# USB-PD.net
KiCad netlist of a schematic drawn in Altium Designer
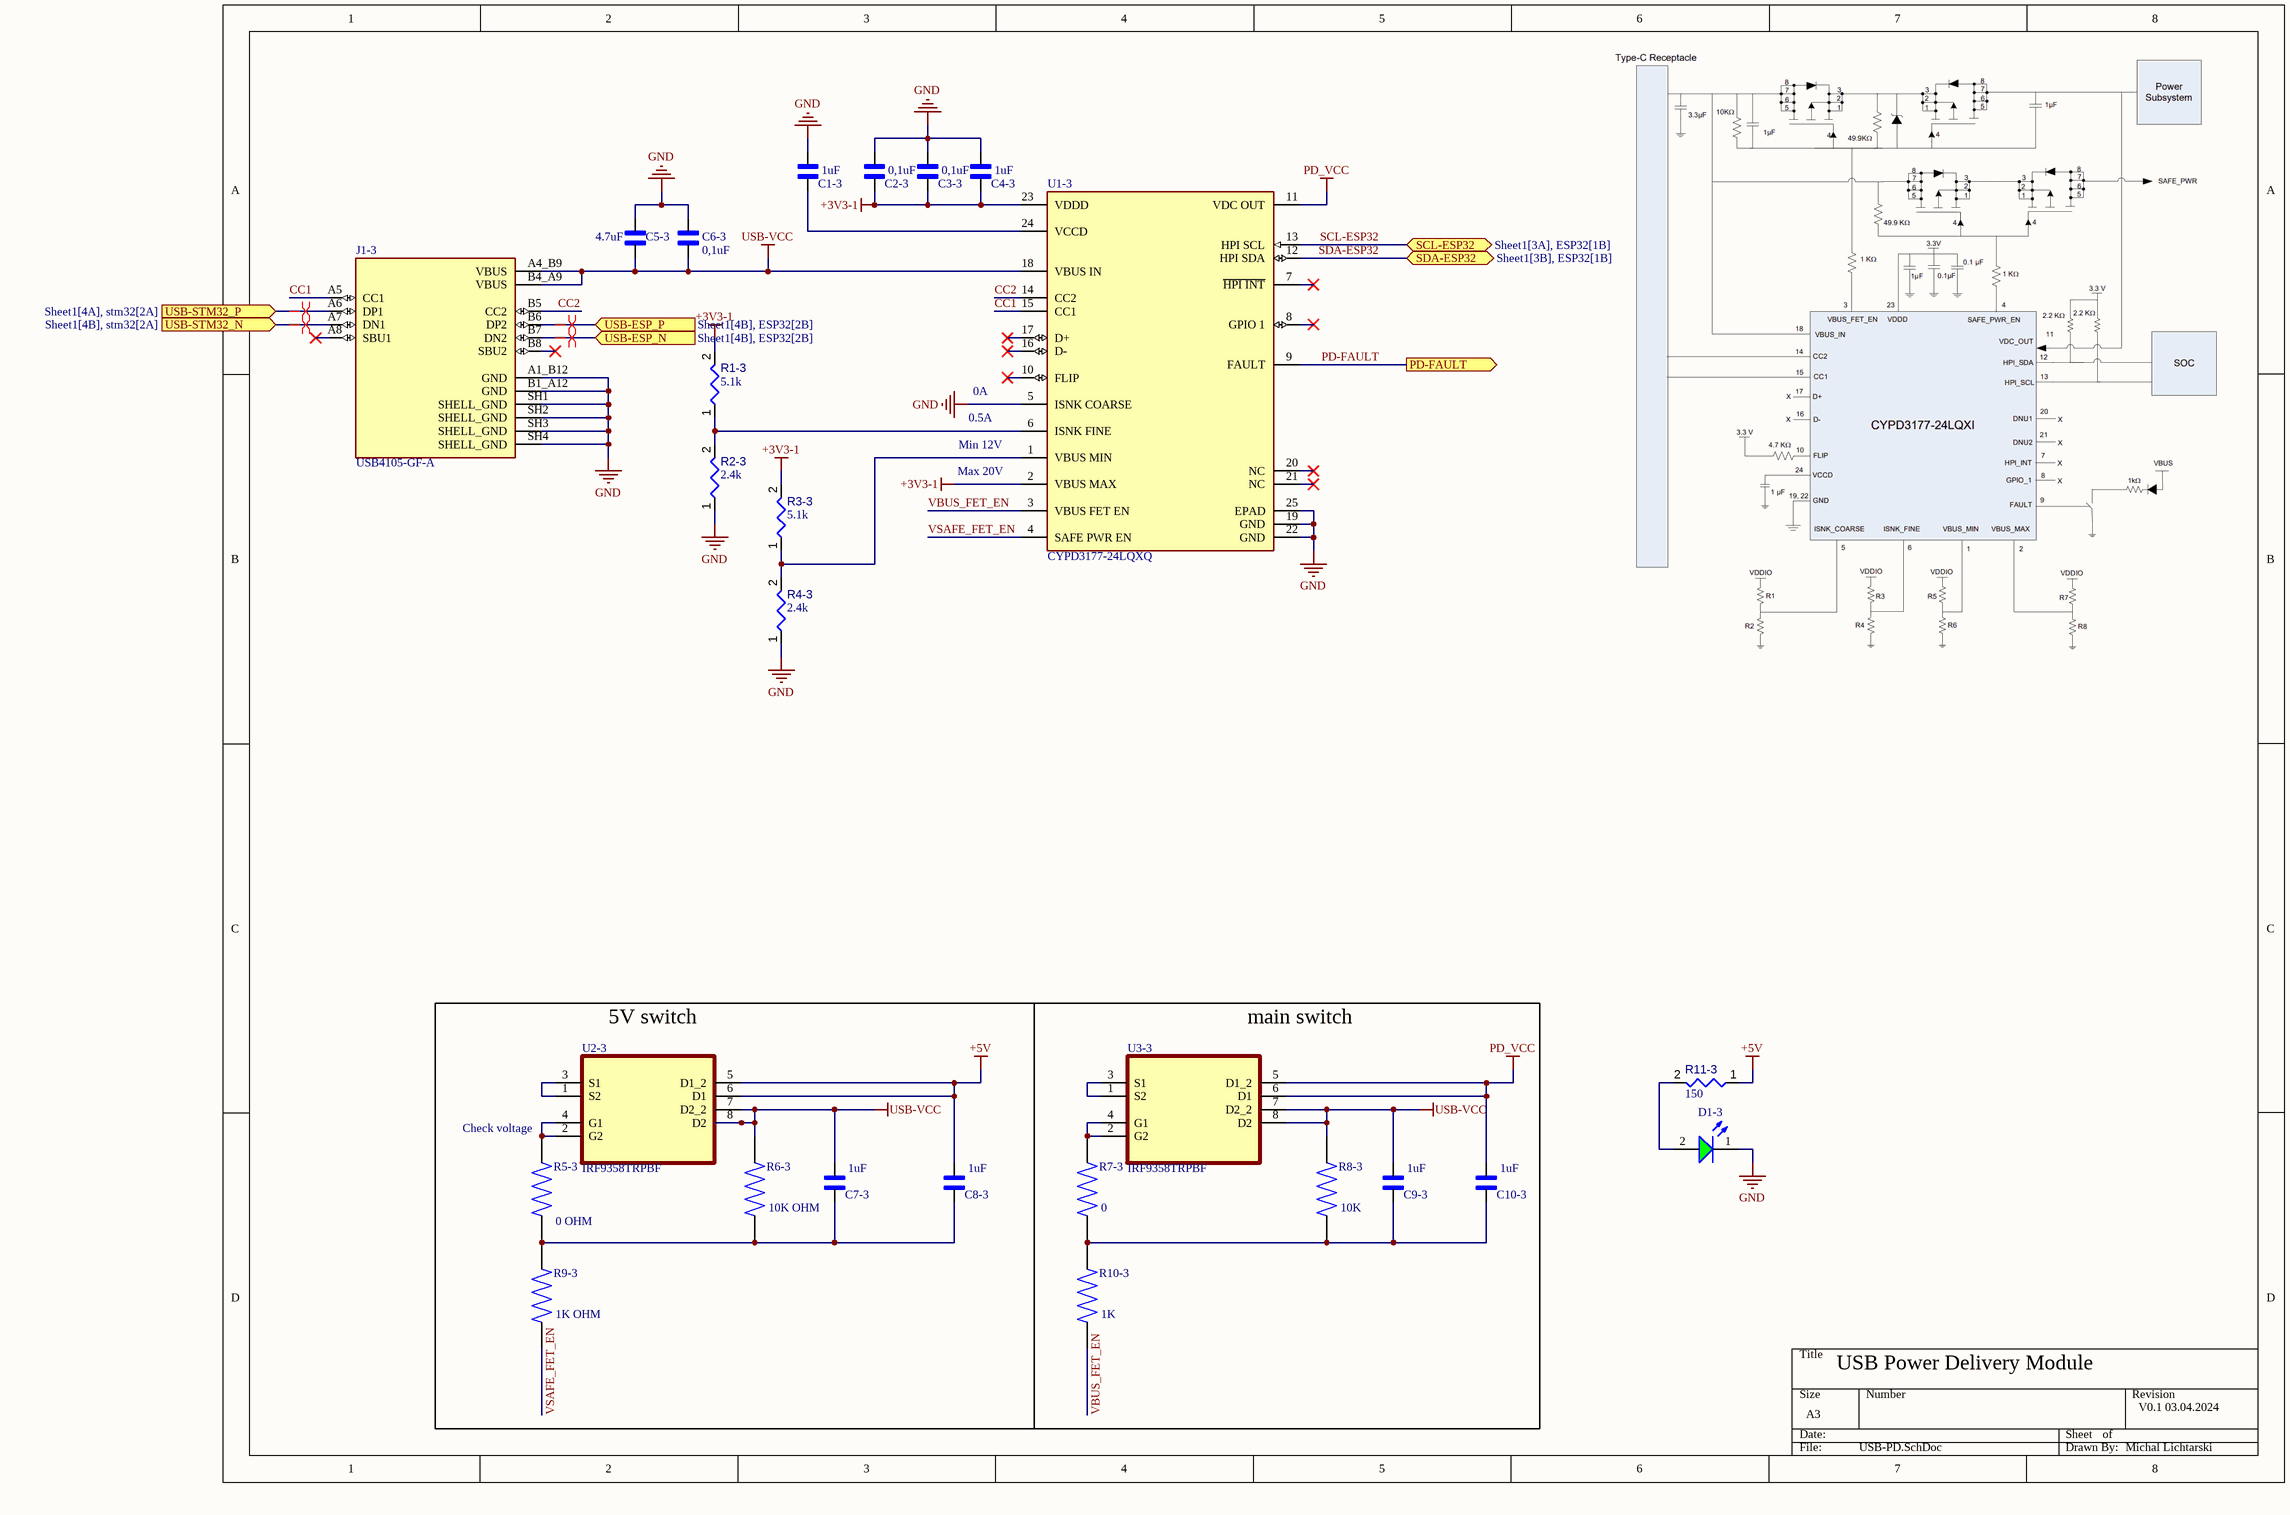
[diagram p0: USB-PD.SchDoc]

(export (version "E")
  (design (tool "Eeschema 10.0.6"))
  (components
    (comp (ref "C1-3")
      (value "1uF 0603")
      (footprint "06035C105KAT2A:CAPC1608X94N")
      (fields
        (field (name "MF") "{'manufacturer': u'KYOCERA AVX Components Corporation'}")
        (field (name "MP") "06035C105KAT2A")
      )
      (libsource (lib "*") (part "06035C105KAT2A"))
    )
    (comp (ref "C2-3")
      (value "0.1uF 0603")
      (footprint "06035C105KAT2A:CAPC1608X94N")
      (fields
        (field (name "MF") "{'manufacturer': u'KYOCERA AVX Components Corporation'}")
        (field (name "MP") "06035C105KAT2A")
      )
      (libsource (lib "*") (part "06035C105KAT2A"))
    )
    (comp (ref "C3-3")
      (value "0.1uF 0603")
      (footprint "06035C105KAT2A:CAPC1608X94N")
      (fields
        (field (name "MF") "{'manufacturer': u'KYOCERA AVX Components Corporation'}")
        (field (name "MP") "06035C105KAT2A")
      )
      (libsource (lib "*") (part "06035C105KAT2A"))
    )
    (comp (ref "C4-3")
      (value "1uF 0603")
      (footprint "06035C105KAT2A:CAPC1608X94N")
      (fields
        (field (name "MF") "{'manufacturer': u'KYOCERA AVX Components Corporation'}")
        (field (name "MP") "06035C105KAT2A")
      )
      (libsource (lib "*") (part "06035C105KAT2A"))
    )
    (comp (ref "C5-3")
      (value "4.7uF 0805 50V")
      (footprint "CL21A475KBQNNNE:CAPC2012X140N")
      (description "Cap Ceramic 4.7uF 50V X5R 10% SMD 0805 85Â°C Embossed Plastic T/R")
      (fields
        (field (name "MF") "{'manufacturer': u'Samsung Electro-Mechanics'}")
        (field (name "MP") "CL21A475KBQNNNE")
      )
      (libsource (lib "*") (part "CL21A475KBQNNNE"))
    )
    (comp (ref "C6-3")
      (value "0.1uF 0603")
      (footprint "06035C105KAT2A:CAPC1608X94N")
      (description "CAP CER 0.1UF 16V X7R 0603")
      (fields
        (field (name "MF") "{'manufacturer': u'KYOCERA AVX Components Corporation'}")
        (field (name "MP") "06035C105KAT2A")
      )
      (libsource (lib "*") (part "06035C105KAT2A"))
    )
    (comp (ref "C7-3")
      (value "1uF 0603")
      (footprint "06035C105KAT2A:CAPC1608X94N")
      (description "CAP CER 1UF 50V X5R 0603")
      (fields
        (field (name "MF") "{'manufacturer': u'KYOCERA AVX Components Corporation'}")
        (field (name "MP") "06035C105KAT2A")
      )
      (libsource (lib "*") (part "06035C105KAT2A"))
    )
    (comp (ref "C8-3")
      (value "1uF 0603")
      (footprint "06035C105KAT2A:CAPC1608X94N")
      (fields
        (field (name "MF") "{'manufacturer': u'KYOCERA AVX Components Corporation'}")
        (field (name "MP") "06035C105KAT2A")
      )
      (libsource (lib "*") (part "06035C105KAT2A"))
    )
    (comp (ref "C9-3")
      (value "1uF 0603")
      (footprint "06035C105KAT2A:CAPC1608X94N")
      (fields
        (field (name "MF") "{'manufacturer': u'KYOCERA AVX Components Corporation'}")
        (field (name "MP") "06035C105KAT2A")
      )
      (libsource (lib "*") (part "06035C105KAT2A"))
    )
    (comp (ref "C10-3")
      (value "1uF 0603")
      (footprint "06035C105KAT2A:CAPC1608X94N")
      (fields
        (field (name "MF") "{'manufacturer': u'KYOCERA AVX Components Corporation'}")
        (field (name "MP") "06035C105KAT2A")
      )
      (libsource (lib "*") (part "06035C105KAT2A"))
    )
    (comp (ref "D1-3")
      (value "150060VS75000")
      (footprint "WL-SMCW_0603_150060xx75000")
      (libsource (lib "Altium Content Vault") (part "LED_Green_2A-1K"))
    )
    (comp (ref "J1-3")
      (value "USB4105-GF-A")
      (footprint "USB4105-GF-A:GCT_USB4105-GF-A")
      (fields (field (name "MF") "{'manufacturer': u'GCT'}"))
      (libsource (lib "USB4105-GF-A") (part "USB4105-GF-A"))
    )
    (comp (ref "R1-3")
      (value "5.1k")
      (footprint "RESC1608X55X25ML10T15")
      (fields
        (field (name "TOLERANCE") "1%")
        (field (name "POWER") "100mW")
        (field (name "Comment") "5.1k 0603")
      )
      (libsource (lib "Michal") (part "RES-2"))
    )
    (comp (ref "R2-3")
      (value "2.4k")
      (footprint "RESC1608X55X25ML10T15")
      (fields
        (field (name "TOLERANCE") "1%")
        (field (name "POWER") "100mW")
        (field (name "Comment") "2.4k 0603")
      )
      (libsource (lib "Michal") (part "RES-2"))
    )
    (comp (ref "R3-3")
      (value "5.1k")
      (footprint "RESC1608X55X25ML10T15")
      (fields
        (field (name "TOLERANCE") "1%")
        (field (name "POWER") "100mW")
        (field (name "Comment") "5.1k 0603")
      )
      (libsource (lib "Michal") (part "RES-2"))
    )
    (comp (ref "R4-3")
      (value "2.4k")
      (footprint "RESC1608X55X25ML10T15")
      (fields
        (field (name "TOLERANCE") "1%")
        (field (name "POWER") "100mW")
        (field (name "Comment") "2.4k 0603")
      )
      (libsource (lib "Michal") (part "RES-2"))
    )
    (comp (ref "R5-3")
      (value "0 0603")
      (footprint "ERJ-3GEY0R00V:RES_ERJ-3GEY0R00V")
      (fields (field (name "MF") "{'manufacturer': u'Panasonic'}") (field (name "MP") "ERJ-3GEY0R00V"))
      (libsource (lib "*") (part "ERJ-3GEY0R00V"))
    )
    (comp (ref "R6-3")
      (value "10k 0603")
      (footprint "RC0603FR-0710KL:RESC1607X60N")
      (fields (field (name "MF") "{'manufacturer': u'Yageo'}") (field (name "MP") "RC0603FR-0710KL"))
      (libsource (lib "*") (part "RC0603FR-0710KL"))
    )
    (comp (ref "R7-3")
      (value "0 0603")
      (footprint "ERJ-3GEY0R00V:RES_ERJ-3GEY0R00V")
      (fields (field (name "MF") "{'manufacturer': u'Panasonic'}") (field (name "MP") "ERJ-3GEY0R00V"))
      (libsource (lib "*") (part "ERJ-3GEY0R00V"))
    )
    (comp (ref "R8-3")
      (value "10k 0603")
      (footprint "RC0603FR-0710KL:RESC1607X60N")
      (fields (field (name "MF") "{'manufacturer': u'Yageo'}") (field (name "MP") "RC0603FR-0710KL"))
      (libsource (lib "*") (part "RC0603FR-0710KL"))
    )
    (comp (ref "R9-3")
      (value "1k 0603")
      (footprint "ERJ-3EKF1001V:RES_ERJ3EKF1001V")
      (fields (field (name "MF") "{'manufacturer': u'Panasonic'}") (field (name "MP") "ERJ3EKF1001V"))
      (libsource (lib "*") (part "ERJ3EKF1001V"))
    )
    (comp (ref "R10-3")
      (value "1k 0603")
      (footprint "ERJ-3EKF1001V:RES_ERJ3EKF1001V")
      (description "RES SMD 1K OHM 1% 1/10W 0603")
      (fields (field (name "MF") "{'manufacturer': u'Panasonic'}") (field (name "MP") "ERJ3EKF1001V"))
      (libsource (lib "*") (part "ERJ3EKF1001V"))
    )
    (comp (ref "R11-3")
      (value "150")
      (footprint "RESC1608X55X25ML10T15")
      (fields
        (field (name "TOLERANCE") "1%")
        (field (name "POWER") "100mW")
        (field (name "Comment") "150 0603")
      )
      (libsource (lib "Michal") (part "RES-2"))
    )
    (comp (ref "U1-3")
      (value "CYPD3177-24LQXQ")
      (footprint "FP-002-16934-IPC_C")
      (description "IC USB TYPE-C PORT CONTROL 24QFN")
      (libsource (lib "Altium Content Vault") (part "568390810166e80f7277aa93be1c0e6"))
    )
    (comp (ref "U2-3")
      (value "IRF9358TRPBF")
      (footprint "IRF9358TRPBF:SOIC127P600X175-8N")
      (description "HEXFET Power MOSFET")
      (fields (field (name "MF") "{'manufacturer': u'Infineon'}"))
      (libsource (lib "IRF9358TRPBF") (part "IRF9358TRPBF"))
    )
    (comp (ref "U3-3")
      (value "IRF9358TRPBF")
      (footprint "IRF9358TRPBF:SOIC127P600X175-8N")
      (description "HEXFET Power MOSFET")
      (fields (field (name "MF") "{'manufacturer': u'Infineon'}"))
      (libsource (lib "IRF9358TRPBF") (part "IRF9358TRPBF"))
    )
  )
  (nets
    (net (code "1") (name "+3V3-1") (class "Default")
      (node (ref "C2-3") (pin "1") (pinfunction "1_1") (pintype "passive"))
      (node (ref "C3-3") (pin "1") (pinfunction "1_1") (pintype "passive"))
      (node (ref "C4-3") (pin "1") (pinfunction "1_1") (pintype "passive"))
      (node (ref "R1-3") (pin "2") (pinfunction "2_2") (pintype "passive"))
      (node (ref "R3-3") (pin "2") (pinfunction "2_2") (pintype "passive"))
      (node (ref "U1-3") (pin "2") (pinfunction "VBUS_MAX_2") (pintype "passive"))
      (node (ref "U1-3") (pin "23") (pinfunction "VDDD_23") (pintype "power_in"))
    )
    (net (code "2") (name "+5V") (class "Default")
      (node (ref "C8-3") (pin "2") (pinfunction "2_2") (pintype "passive"))
      (node (ref "R11-3") (pin "1") (pinfunction "1_1") (pintype "passive"))
      (node (ref "U2-3") (pin "5") (pinfunction "D1_2_5") (pintype "passive"))
      (node (ref "U2-3") (pin "6") (pinfunction "D1_6") (pintype "passive"))
    )
    (net (code "3") (name "/CC1") (class "Default")
      (node (ref "J1-3") (pin "A5") (pinfunction "CC1_A5") (pintype "bidirectional"))
      (node (ref "U1-3") (pin "15") (pinfunction "CC1_15") (pintype "passive"))
    )
    (net (code "4") (name "/CC2") (class "Default")
      (node (ref "J1-3") (pin "B5") (pinfunction "CC2_B5") (pintype "bidirectional"))
      (node (ref "U1-3") (pin "14") (pinfunction "CC2_14") (pintype "passive"))
    )
    (net (code "5") (name "/PD-FAULT") (class "Default")
      (node (ref "U1-3") (pin "9") (pinfunction "FAULT_9") (pintype "open_collector"))
    )
    (net (code "6") (name "/SCL-ESP32") (class "Default")
      (node (ref "U1-3") (pin "13") (pinfunction "HPI_SCL_13") (pintype "input"))
    )
    (net (code "7") (name "/SDA-ESP32") (class "Default")
      (node (ref "U1-3") (pin "12") (pinfunction "HPI_SDA_12") (pintype "bidirectional"))
    )
    (net (code "8") (name "/USB-ESP_N") (class "Default")
      (node (ref "J1-3") (pin "B7") (pinfunction "DN2_B7") (pintype "bidirectional"))
    )
    (net (code "9") (name "/USB-ESP_P") (class "Default")
      (node (ref "J1-3") (pin "B6") (pinfunction "DP2_B6") (pintype "bidirectional"))
    )
    (net (code "10") (name "/USB-STM32_N") (class "Default")
      (node (ref "J1-3") (pin "A7") (pinfunction "DN1_A7") (pintype "bidirectional"))
    )
    (net (code "11") (name "/USB-STM32_P") (class "Default")
      (node (ref "J1-3") (pin "A6") (pinfunction "DP1_A6") (pintype "bidirectional"))
    )
    (net (code "12") (name "/VBUS_FET_EN") (class "Default")
      (node (ref "R10-3") (pin "1") (pinfunction "1_1") (pintype "passive"))
      (node (ref "U1-3") (pin "3") (pinfunction "VBUS_FET_EN_3") (pintype "passive"))
    )
    (net (code "13") (name "/VSAFE_FET_EN") (class "Default")
      (node (ref "R9-3") (pin "1") (pinfunction "1_1") (pintype "passive"))
      (node (ref "U1-3") (pin "4") (pinfunction "SAFE_PWR_EN_4") (pintype "passive"))
    )
    (net (code "14") (name "GND") (class "Default")
      (node (ref "C1-3") (pin "2") (pinfunction "2_2") (pintype "passive"))
      (node (ref "C2-3") (pin "2") (pinfunction "2_2") (pintype "passive"))
      (node (ref "C3-3") (pin "2") (pinfunction "2_2") (pintype "passive"))
      (node (ref "C4-3") (pin "2") (pinfunction "2_2") (pintype "passive"))
      (node (ref "C5-3") (pin "1") (pinfunction "1_1") (pintype "passive"))
      (node (ref "C6-3") (pin "2") (pinfunction "2_2") (pintype "passive"))
      (node (ref "D1-3") (pin "1") (pinfunction "K_1") (pintype "passive"))
      (node (ref "J1-3") (pin "A1_B12") (pinfunction "GND_A1_B12") (pintype "power_in"))
      (node (ref "J1-3") (pin "B1_A12") (pinfunction "GND_B1_A12") (pintype "power_in"))
      (node (ref "J1-3") (pin "SH1") (pinfunction "SHELL_GND_SH1") (pintype "power_in"))
      (node (ref "J1-3") (pin "SH2") (pinfunction "SHELL_GND_SH2") (pintype "power_in"))
      (node (ref "J1-3") (pin "SH3") (pinfunction "SHELL_GND_SH3") (pintype "power_in"))
      (node (ref "J1-3") (pin "SH4") (pinfunction "SHELL_GND_SH4") (pintype "power_in"))
      (node (ref "R2-3") (pin "1") (pinfunction "1_1") (pintype "passive"))
      (node (ref "R4-3") (pin "1") (pinfunction "1_1") (pintype "passive"))
      (node (ref "U1-3") (pin "19") (pinfunction "GND_19") (pintype "power_in"))
      (node (ref "U1-3") (pin "22") (pinfunction "GND_22") (pintype "power_in"))
      (node (ref "U1-3") (pin "25") (pinfunction "EPAD_25") (pintype "power_in"))
      (node (ref "U1-3") (pin "5") (pinfunction "ISNK_COARSE_5") (pintype "passive"))
    )
    (net (code "15") (name "Net-(C7-3-Pad1)") (class "Default")
      (node (ref "C7-3") (pin "1") (pinfunction "1_1") (pintype "passive"))
      (node (ref "C8-3") (pin "1") (pinfunction "1_1") (pintype "passive"))
      (node (ref "R5-3") (pin "1") (pinfunction "1_1") (pintype "passive"))
      (node (ref "R6-3") (pin "1") (pinfunction "1_1") (pintype "passive"))
      (node (ref "R9-3") (pin "2") (pinfunction "2_2") (pintype "passive"))
    )
    (net (code "16") (name "Net-(C10-3-Pad1)") (class "Default")
      (node (ref "C10-3") (pin "1") (pinfunction "1_1") (pintype "passive"))
      (node (ref "C9-3") (pin "1") (pinfunction "1_1") (pintype "passive"))
      (node (ref "R10-3") (pin "2") (pinfunction "2_2") (pintype "passive"))
      (node (ref "R7-3") (pin "1") (pinfunction "1_1") (pintype "passive"))
      (node (ref "R8-3") (pin "1") (pinfunction "1_1") (pintype "passive"))
    )
    (net (code "17") (name "Net-(D1-3-A)") (class "Default")
      (node (ref "D1-3") (pin "2") (pinfunction "A_2") (pintype "passive"))
      (node (ref "R11-3") (pin "2") (pinfunction "2_2") (pintype "passive"))
    )
    (net (code "18") (name "Net-(U1-3-ISNK_FINE)") (class "Default")
      (node (ref "R1-3") (pin "1") (pinfunction "1_1") (pintype "passive"))
      (node (ref "R2-3") (pin "2") (pinfunction "2_2") (pintype "passive"))
      (node (ref "U1-3") (pin "6") (pinfunction "ISNK_FINE_6") (pintype "passive"))
    )
    (net (code "19") (name "Net-(U1-3-VBUS_MIN)") (class "Default")
      (node (ref "R3-3") (pin "1") (pinfunction "1_1") (pintype "passive"))
      (node (ref "R4-3") (pin "2") (pinfunction "2_2") (pintype "passive"))
      (node (ref "U1-3") (pin "1") (pinfunction "VBUS_MIN_1") (pintype "passive"))
    )
    (net (code "20") (name "Net-(U1-3-VCCD)") (class "Default")
      (node (ref "C1-3") (pin "1") (pinfunction "1_1") (pintype "passive"))
      (node (ref "U1-3") (pin "24") (pinfunction "VCCD_24") (pintype "power_in"))
    )
    (net (code "21") (name "Net-(U2-3-G1)") (class "Default")
      (node (ref "R5-3") (pin "2") (pinfunction "2_2") (pintype "passive"))
      (node (ref "U2-3") (pin "2") (pinfunction "G2_2") (pintype "passive"))
      (node (ref "U2-3") (pin "4") (pinfunction "G1_4") (pintype "passive"))
    )
    (net (code "22") (name "Net-(U2-3-S1)") (class "Default")
      (node (ref "U2-3") (pin "1") (pinfunction "S2_1") (pintype "passive"))
      (node (ref "U2-3") (pin "3") (pinfunction "S1_3") (pintype "passive"))
    )
    (net (code "23") (name "Net-(U3-3-G1)") (class "Default")
      (node (ref "R7-3") (pin "2") (pinfunction "2_2") (pintype "passive"))
      (node (ref "U3-3") (pin "2") (pinfunction "G2_2") (pintype "passive"))
      (node (ref "U3-3") (pin "4") (pinfunction "G1_4") (pintype "passive"))
    )
    (net (code "24") (name "Net-(U3-3-S1)") (class "Default")
      (node (ref "U3-3") (pin "1") (pinfunction "S2_1") (pintype "passive"))
      (node (ref "U3-3") (pin "3") (pinfunction "S1_3") (pintype "passive"))
    )
    (net (code "25") (name "PD_VCC") (class "Default")
      (node (ref "C10-3") (pin "2") (pinfunction "2_2") (pintype "passive"))
      (node (ref "U1-3") (pin "11") (pinfunction "VDC_OUT_11") (pintype "passive"))
      (node (ref "U3-3") (pin "5") (pinfunction "D1_2_5") (pintype "passive"))
      (node (ref "U3-3") (pin "6") (pinfunction "D1_6") (pintype "passive"))
    )
    (net (code "26") (name "USB-VCC") (class "Default")
      (node (ref "C5-3") (pin "2") (pinfunction "2_2") (pintype "passive"))
      (node (ref "C6-3") (pin "1") (pinfunction "1_1") (pintype "passive"))
      (node (ref "C7-3") (pin "2") (pinfunction "2_2") (pintype "passive"))
      (node (ref "C9-3") (pin "2") (pinfunction "2_2") (pintype "passive"))
      (node (ref "J1-3") (pin "A4_B9") (pinfunction "VBUS_A4_B9") (pintype "power_in"))
      (node (ref "J1-3") (pin "B4_A9") (pinfunction "VBUS_B4_A9") (pintype "power_in"))
      (node (ref "R6-3") (pin "2") (pinfunction "2_2") (pintype "passive"))
      (node (ref "R8-3") (pin "2") (pinfunction "2_2") (pintype "passive"))
      (node (ref "U1-3") (pin "18") (pinfunction "VBUS_IN_18") (pintype "power_in"))
      (node (ref "U2-3") (pin "7") (pinfunction "D2_2_7") (pintype "passive"))
      (node (ref "U2-3") (pin "8") (pinfunction "D2_8") (pintype "passive"))
      (node (ref "U3-3") (pin "7") (pinfunction "D2_2_7") (pintype "passive"))
      (node (ref "U3-3") (pin "8") (pinfunction "D2_8") (pintype "passive"))
    )
    (net (code "27") (name "unconnected-(J1-3-SBU1-PadA8)") (class "Default")
      (node (ref "J1-3") (pin "A8") (pinfunction "SBU1_A8") (pintype "bidirectional+no_connect"))
    )
    (net (code "28") (name "unconnected-(J1-3-SBU2-PadB8)") (class "Default")
      (node (ref "J1-3") (pin "B8") (pinfunction "SBU2_B8") (pintype "bidirectional+no_connect"))
    )
    (net (code "29") (name "unconnected-(U1-3-D+-Pad17)") (class "Default")
      (node (ref "U1-3") (pin "17") (pinfunction "D+_17") (pintype "bidirectional+no_connect"))
    )
    (net (code "30") (name "unconnected-(U1-3-D--Pad16)") (class "Default")
      (node (ref "U1-3") (pin "16") (pinfunction "D-_16") (pintype "bidirectional+no_connect"))
    )
    (net (code "31") (name "unconnected-(U1-3-FLIP-Pad10)") (class "Default")
      (node (ref "U1-3") (pin "10") (pinfunction "FLIP_10") (pintype "bidirectional+no_connect"))
    )
    (net (code "32") (name "unconnected-(U1-3-GPIO_1-Pad8)") (class "Default")
      (node (ref "U1-3") (pin "8") (pinfunction "GPIO_1_8") (pintype "bidirectional+no_connect"))
    )
    (net (code "33") (name "unconnected-(U1-3-NC-Pad20)") (class "Default")
      (node (ref "U1-3") (pin "20") (pinfunction "NC_20") (pintype "passive+no_connect"))
    )
    (net (code "34") (name "unconnected-(U1-3-NC-Pad21)") (class "Default")
      (node (ref "U1-3") (pin "21") (pinfunction "NC_21") (pintype "passive+no_connect"))
    )
    (net (code "35") (name "unconnected-(U1-3-~{HPI_INT}-Pad7)") (class "Default")
      (node (ref "U1-3") (pin "7") (pinfunction "~{HPI_INT}_7") (pintype "passive+no_connect"))
    )
  )
)
